# 25_LMS3_RX1_BB_ADC.net
KiCad netlist of a schematic drawn in Altium Designer
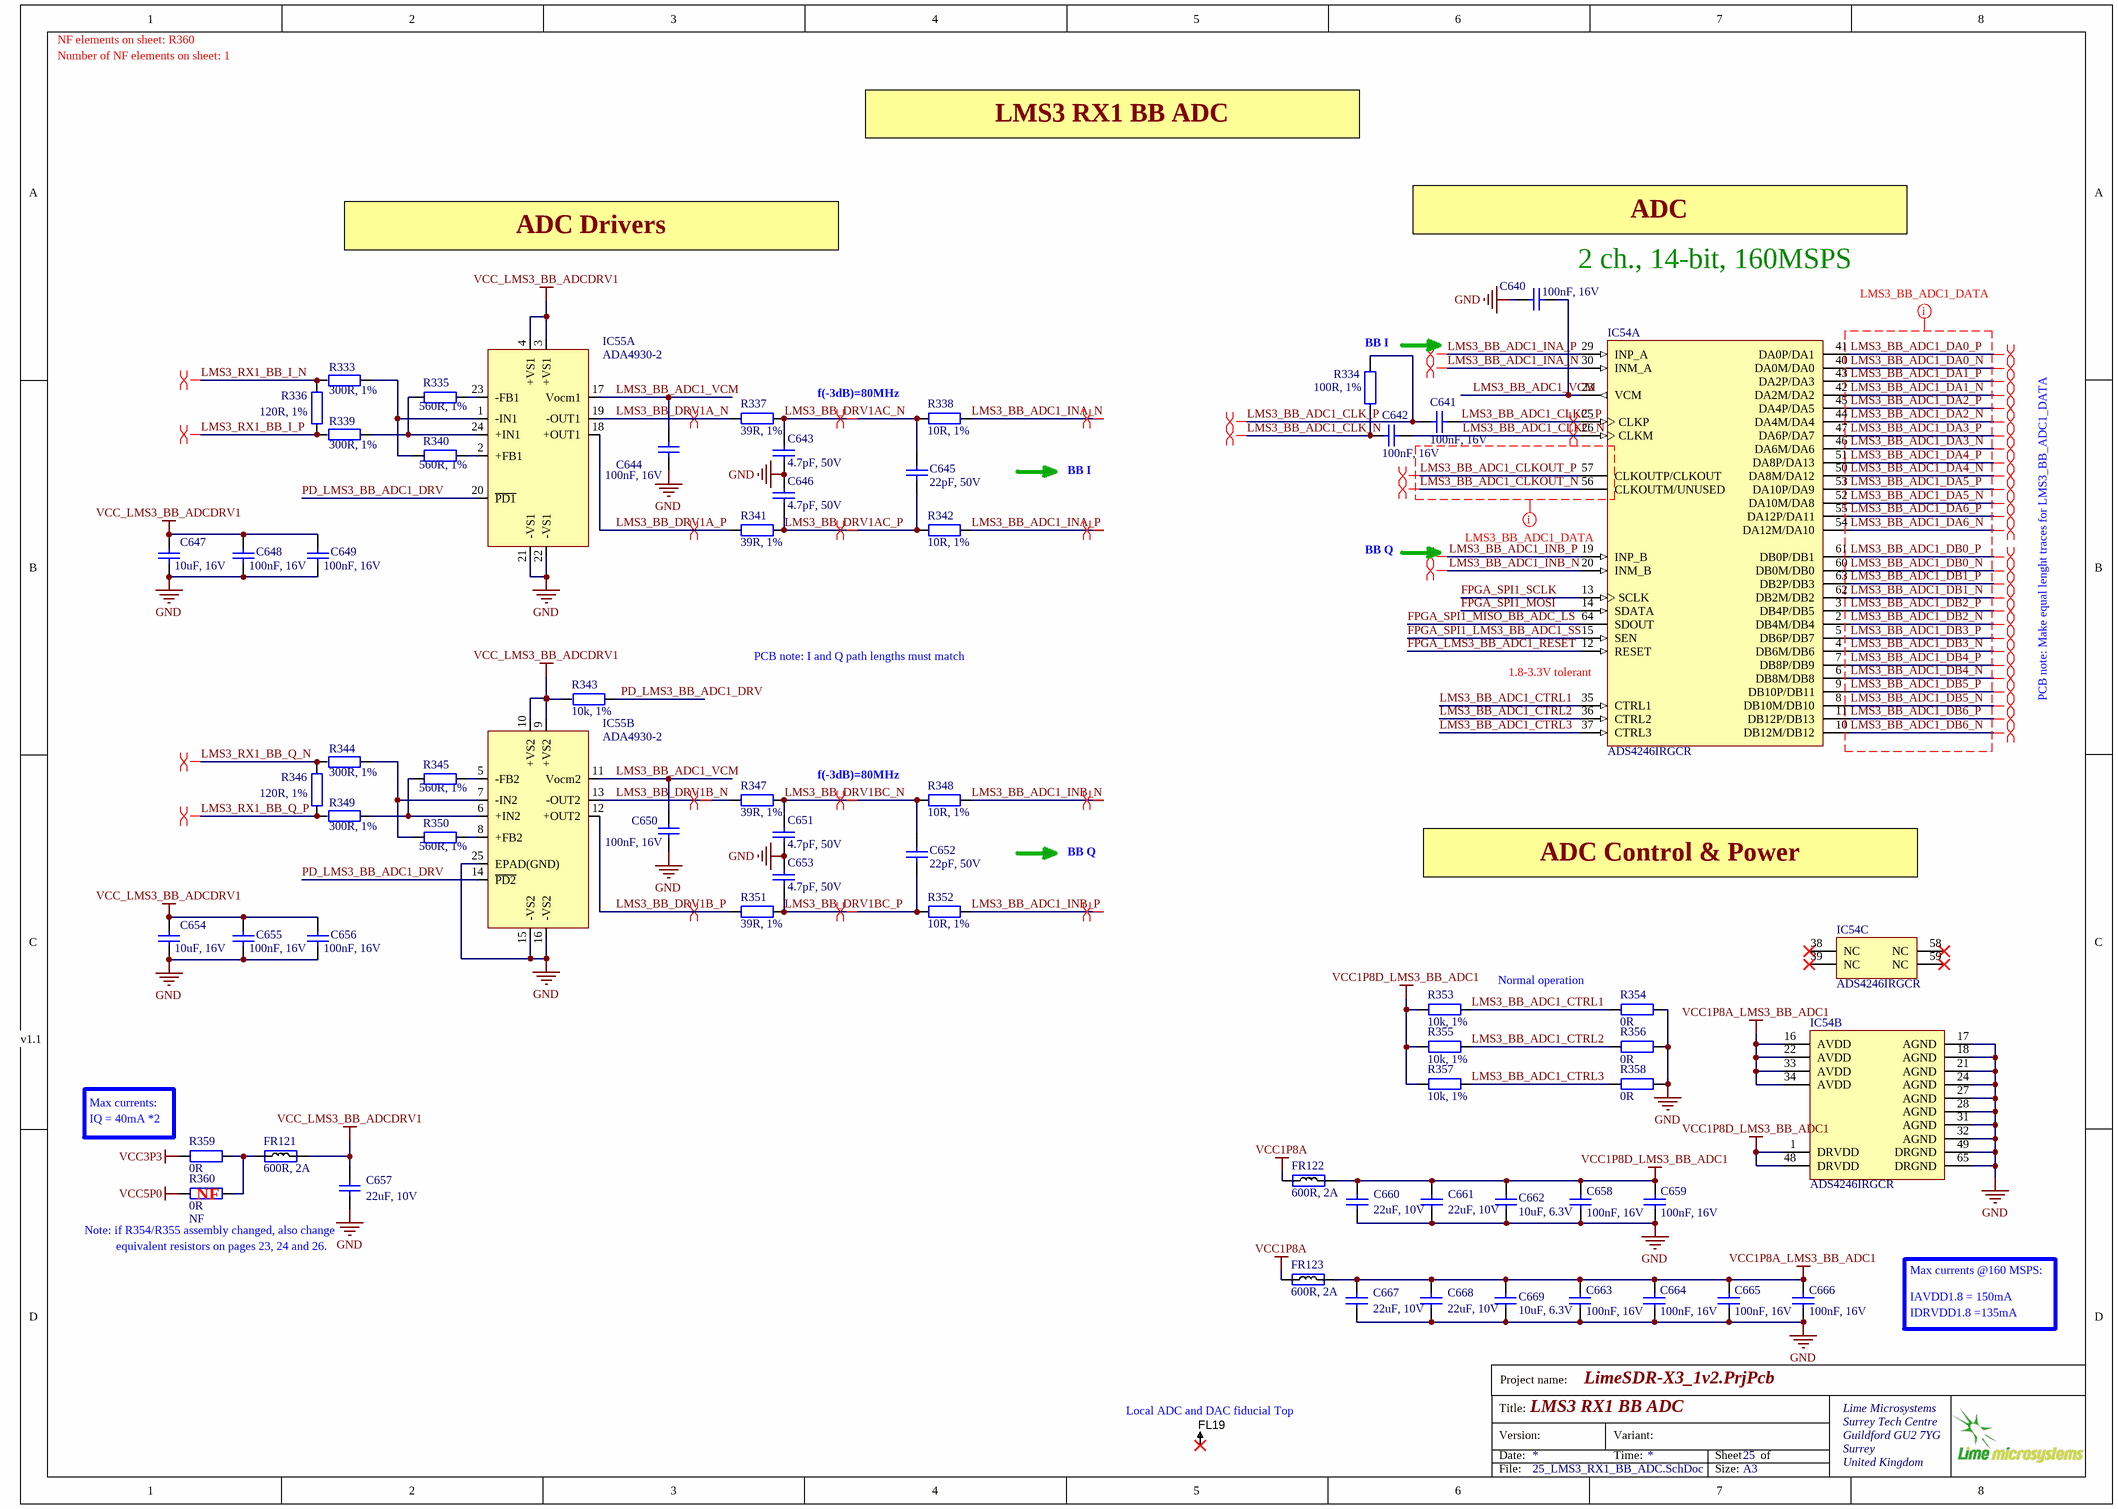
[diagram p0: 25_LMS3_RX1_BB_ADC.SchDoc]

(export (version "E")
  (design (tool "Eeschema 10.0.6"))
  (components
    (comp (ref "C640")
      (value "100nF, 16V")
      (footprint "CAP0402")
      (fields (field (name "TOLERANCE") "10 %") (field (name "MANUFACTURER") "Murata Electronics"))
      (libsource (lib "") (part "Cap_0603_2"))
    )
    (comp (ref "C641")
      (value "100nF, 16V")
      (footprint "CAP0402")
      (fields (field (name "TOLERANCE") "10 %") (field (name "MANUFACTURER") "Murata Electronics"))
      (libsource (lib "") (part "Cap_0603_2"))
    )
    (comp (ref "C642")
      (value "100nF, 16V")
      (footprint "CAP0402")
      (fields (field (name "TOLERANCE") "10 %") (field (name "MANUFACTURER") "Murata Electronics"))
      (libsource (lib "") (part "Cap_0603_1"))
    )
    (comp (ref "C643")
      (value "4.7pF, 50V")
      (footprint "CAP0402")
      (fields (field (name "MANUFACTURER") "MURATA"))
      (libsource (lib "LimeMicroAltiumLib_schLib") (part "Cap_0402"))
    )
    (comp (ref "C644")
      (value "100nF, 16V")
      (footprint "CAP0402")
      (fields (field (name "TOLERANCE") "10 %") (field (name "MANUFACTURER") "Murata Electronics"))
      (libsource (lib "") (part "Cap_0603_1"))
    )
    (comp (ref "C645")
      (value "22pF, 50V")
      (footprint "CAP0402")
      (fields (field (name "TOLERANCE") "±5%") (field (name "MANUFACTURER") "Yageo"))
      (libsource (lib "") (part "Cap_0402_1"))
    )
    (comp (ref "C646")
      (value "4.7pF, 50V")
      (footprint "CAP0402")
      (fields (field (name "MANUFACTURER") "MURATA"))
      (libsource (lib "LimeMicroAltiumLib_schLib") (part "Cap_0402"))
    )
    (comp (ref "C647")
      (value "10uF, 16V")
      (footprint "CAP0603")
      (fields (field (name "MANUFACTURER") "Yageo") (field (name "TOLERANCE") "±20%"))
      (libsource (lib "LimeMicroAltiumLib_schLib") (part "Cap_0603"))
    )
    (comp (ref "C648")
      (value "100nF, 16V")
      (footprint "CAP0402")
      (fields (field (name "TOLERANCE") "10 %") (field (name "MANUFACTURER") "Murata Electronics"))
      (libsource (lib "") (part "Cap_0603_1"))
    )
    (comp (ref "C649")
      (value "100nF, 16V")
      (footprint "CAP0402")
      (fields (field (name "TOLERANCE") "10 %") (field (name "MANUFACTURER") "Murata Electronics"))
      (libsource (lib "") (part "Cap_0603_1"))
    )
    (comp (ref "C650")
      (value "100nF, 16V")
      (footprint "CAP0402")
      (fields (field (name "TOLERANCE") "10 %") (field (name "MANUFACTURER") "Murata Electronics"))
      (libsource (lib "") (part "Cap_0603_5"))
    )
    (comp (ref "C651")
      (value "4.7pF, 50V")
      (footprint "CAP0402")
      (fields (field (name "MANUFACTURER") "MURATA"))
      (libsource (lib "LimeMicroAltiumLib_schLib") (part "Cap_0402"))
    )
    (comp (ref "C652")
      (value "22pF, 50V")
      (footprint "CAP0402")
      (fields (field (name "TOLERANCE") "±5%") (field (name "MANUFACTURER") "Yageo"))
      (libsource (lib "") (part "Cap_0402_1"))
    )
    (comp (ref "C653")
      (value "4.7pF, 50V")
      (footprint "CAP0402")
      (fields (field (name "MANUFACTURER") "MURATA"))
      (libsource (lib "LimeMicroAltiumLib_schLib") (part "Cap_0402"))
    )
    (comp (ref "C654")
      (value "10uF, 16V")
      (footprint "CAP0603")
      (fields (field (name "MANUFACTURER") "Yageo") (field (name "TOLERANCE") "±20%"))
      (libsource (lib "LimeMicroAltiumLib_schLib") (part "Cap_0603"))
    )
    (comp (ref "C655")
      (value "100nF, 16V")
      (footprint "CAP0402")
      (fields (field (name "TOLERANCE") "10 %") (field (name "MANUFACTURER") "Murata Electronics"))
      (libsource (lib "") (part "Cap_0603_1"))
    )
    (comp (ref "C656")
      (value "100nF, 16V")
      (footprint "CAP0402")
      (fields (field (name "TOLERANCE") "10 %") (field (name "MANUFACTURER") "Murata Electronics"))
      (libsource (lib "") (part "Cap_0603_1"))
    )
    (comp (ref "C657")
      (value "22uF, 10V")
      (footprint "CAP0603")
      (fields (field (name "TOLERANCE") "20 %") (field (name "MANUFACTURER") "TDK Corporation"))
      (libsource (lib "") (part "Cap_0603_3"))
    )
    (comp (ref "C658")
      (value "100nF, 16V")
      (footprint "CAP0402")
      (fields (field (name "TOLERANCE") "10 %") (field (name "MANUFACTURER") "Murata Electronics"))
      (libsource (lib "LimeFPGAboard_schLib") (part "Cap_0603"))
    )
    (comp (ref "C659")
      (value "100nF, 16V")
      (footprint "CAP0402")
      (fields (field (name "TOLERANCE") "10 %") (field (name "MANUFACTURER") "Murata Electronics"))
      (libsource (lib "LimeFPGAboard_schLib") (part "Cap_0603"))
    )
    (comp (ref "C660")
      (value "22uF, 10V")
      (footprint "CAP0603")
      (fields (field (name "TOLERANCE") "20 %") (field (name "MANUFACTURER") "TDK Corporation"))
      (libsource (lib "LimeFPGAboard_schLib") (part "Cap_0603"))
    )
    (comp (ref "C661")
      (value "22uF, 10V")
      (footprint "CAP0603")
      (fields (field (name "TOLERANCE") "20 %") (field (name "MANUFACTURER") "TDK Corporation"))
      (libsource (lib "LimeFPGAboard_schLib") (part "Cap_0603"))
    )
    (comp (ref "C662")
      (value "10uF, 6.3V")
      (footprint "CAP0603")
      (fields (field (name "TOLERANCE") "±20%") (field (name "MANUFACTURER") "Yageo"))
      (libsource (lib "") (part "Cap_0603_6"))
    )
    (comp (ref "C663")
      (value "100nF, 16V")
      (footprint "CAP0402")
      (fields (field (name "TOLERANCE") "10 %") (field (name "MANUFACTURER") "Murata Electronics"))
      (libsource (lib "") (part "Cap_0603_4"))
    )
    (comp (ref "C664")
      (value "100nF, 16V")
      (footprint "CAP0402")
      (fields (field (name "TOLERANCE") "10 %") (field (name "MANUFACTURER") "Murata Electronics"))
      (libsource (lib "") (part "Cap_0603_4"))
    )
    (comp (ref "C665")
      (value "100nF, 16V")
      (footprint "CAP0402")
      (fields (field (name "TOLERANCE") "10 %") (field (name "MANUFACTURER") "Murata Electronics"))
      (libsource (lib "") (part "Cap_0603_4"))
    )
    (comp (ref "C666")
      (value "100nF, 16V")
      (footprint "CAP0402")
      (fields (field (name "TOLERANCE") "10 %") (field (name "MANUFACTURER") "Murata Electronics"))
      (libsource (lib "") (part "Cap_0603_4"))
    )
    (comp (ref "C667")
      (value "22uF, 10V")
      (footprint "CAP0603")
      (fields (field (name "TOLERANCE") "20 %") (field (name "MANUFACTURER") "TDK Corporation"))
      (libsource (lib "") (part "Cap_0603_4"))
    )
    (comp (ref "C668")
      (value "22uF, 10V")
      (footprint "CAP0603")
      (fields (field (name "TOLERANCE") "20 %") (field (name "MANUFACTURER") "TDK Corporation"))
      (libsource (lib "") (part "Cap_0603_4"))
    )
    (comp (ref "C669")
      (value "10uF, 6.3V")
      (footprint "CAP0603")
      (fields (field (name "TOLERANCE") "±20%") (field (name "MANUFACTURER") "Yageo"))
      (libsource (lib "") (part "Cap_0603_7"))
    )
    (comp (ref "FL19")
      (value "Fiducial")
      (footprint "Fiducial_local")
      (libsource (lib "LimeMicroAltiumLib_schLib") (part "Fiducial"))
    )
    (comp (ref "FR121")
      (value "600R, 2A")
      (footprint "RES0805")
      (fields (field (name "MANUFACTURER") "TDK Corporation"))
      (libsource (lib "LimeMicroAltiumLib_schLib") (part "Ferrite"))
    )
    (comp (ref "FR122")
      (value "600R, 2A")
      (footprint "RES0805")
      (fields (field (name "MANUFACTURER") "TDK Corporation"))
      (libsource (lib "LimeFPGAboard_schLib") (part "Ferrite"))
    )
    (comp (ref "FR123")
      (value "600R, 2A")
      (footprint "RES0805")
      (fields (field (name "MANUFACTURER") "TDK Corporation"))
      (libsource (lib "LimeFPGAboard_schLib") (part "Ferrite"))
    )
    (comp (ref "IC54")
      (value "ADS4246IRGCR")
      (footprint "TI-RGC64-7400X7400TP_V")
      (description "14-Bit 160 MSPS Dual Low Power ADC, -40 to 85 degC, 64-pin QFN (RGC64), Green (RoHS & no Sb/Br)")
      (fields (field (name "MANUFACTURER") "Texas Instruments"))
      (libsource (lib "") (part "ADS4246IRGCR_1"))
    )
    (comp (ref "IC55")
      (value "ADA4930-2")
      (footprint "ADA4930-2_LFCSP-24")
      (fields (field (name "MANUFACTURER") "Analog Devices Inc."))
      (libsource (lib "LimeMicroAltiumLib_schLib") (part "ADA4930-2"))
    )
    (comp (ref "R333")
      (value "300R, 1%")
      (footprint "RES0402")
      (fields (field (name "TOLERANCE") "±1%") (field (name "MANUFACTURER") "Vishay Dale"))
      (libsource (lib "LimeFPGAboard_schLib") (part "Res_0402"))
    )
    (comp (ref "R334")
      (value "100R, 1%")
      (footprint "RES0402")
      (fields (field (name "TOLERANCE") "±1%") (field (name "MANUFACTURER") "Stackpole Electronics Inc."))
      (libsource (lib "LimeFPGAboard_schLib") (part "Res_0402"))
    )
    (comp (ref "R335")
      (value "560R, 1%")
      (footprint "RES0402")
      (fields (field (name "TOLERANCE") "±1%") (field (name "MANUFACTURER") "Vishay Dale"))
      (libsource (lib "LimeFPGAboard_schLib") (part "Res_0402"))
    )
    (comp (ref "R336")
      (value "120R, 1%")
      (footprint "RES0402")
      (fields (field (name "MANUFACTURER") "Yageo") (field (name "TOLERANCE") "1%"))
      (libsource (lib "") (part "Res_0402_1"))
    )
    (comp (ref "R337")
      (value "39R, 1%")
      (footprint "RES0402")
      (fields (field (name "MANUFACTURER") "Yageo") (field (name "TOLERANCE") "1%"))
      (libsource (lib "LimeMicroAltiumLib_schLib") (part "Res_0402"))
    )
    (comp (ref "R338")
      (value "10R, 1%")
      (footprint "RES0402")
      (fields (field (name "TOLERANCE") "1%"))
      (libsource (lib "LimeMicroAltiumLib_schLib") (part "Res_0402"))
    )
    (comp (ref "R339")
      (value "300R, 1%")
      (footprint "RES0402")
      (fields (field (name "TOLERANCE") "±1%") (field (name "MANUFACTURER") "Vishay Dale"))
      (libsource (lib "LimeFPGAboard_schLib") (part "Res_0402"))
    )
    (comp (ref "R340")
      (value "560R, 1%")
      (footprint "RES0402")
      (fields (field (name "TOLERANCE") "±1%") (field (name "MANUFACTURER") "Vishay Dale"))
      (libsource (lib "LimeFPGAboard_schLib") (part "Res_0402"))
    )
    (comp (ref "R341")
      (value "39R, 1%")
      (footprint "RES0402")
      (fields (field (name "MANUFACTURER") "Yageo") (field (name "TOLERANCE") "1%"))
      (libsource (lib "LimeMicroAltiumLib_schLib") (part "Res_0402"))
    )
    (comp (ref "R342")
      (value "10R, 1%")
      (footprint "RES0402")
      (fields (field (name "TOLERANCE") "1%"))
      (libsource (lib "LimeMicroAltiumLib_schLib") (part "Res_0402"))
    )
    (comp (ref "R343")
      (value "10k, 1%")
      (footprint "RES0402")
      (fields (field (name "MANUFACTURER") "Yageo") (field (name "TOLERANCE") "±1%"))
      (libsource (lib "LimeMicroAltiumLib_schLib") (part "Res_0402"))
    )
    (comp (ref "R344")
      (value "300R, 1%")
      (footprint "RES0402")
      (fields (field (name "TOLERANCE") "±1%") (field (name "MANUFACTURER") "Vishay Dale"))
      (libsource (lib "LimeFPGAboard_schLib") (part "Res_0402"))
    )
    (comp (ref "R345")
      (value "560R, 1%")
      (footprint "RES0402")
      (fields (field (name "TOLERANCE") "±1%") (field (name "MANUFACTURER") "Vishay Dale"))
      (libsource (lib "LimeFPGAboard_schLib") (part "Res_0402"))
    )
    (comp (ref "R346")
      (value "120R, 1%")
      (footprint "RES0402")
      (fields (field (name "MANUFACTURER") "Yageo") (field (name "TOLERANCE") "1%"))
      (libsource (lib "") (part "Res_0402_1"))
    )
    (comp (ref "R347")
      (value "39R, 1%")
      (footprint "RES0402")
      (fields (field (name "MANUFACTURER") "Yageo") (field (name "TOLERANCE") "1%"))
      (libsource (lib "LimeMicroAltiumLib_schLib") (part "Res_0402"))
    )
    (comp (ref "R348")
      (value "10R, 1%")
      (footprint "RES0402")
      (fields (field (name "TOLERANCE") "1%"))
      (libsource (lib "LimeMicroAltiumLib_schLib") (part "Res_0402"))
    )
    (comp (ref "R349")
      (value "300R, 1%")
      (footprint "RES0402")
      (fields (field (name "TOLERANCE") "±1%") (field (name "MANUFACTURER") "Vishay Dale"))
      (libsource (lib "LimeFPGAboard_schLib") (part "Res_0402"))
    )
    (comp (ref "R350")
      (value "560R, 1%")
      (footprint "RES0402")
      (fields (field (name "TOLERANCE") "±1%") (field (name "MANUFACTURER") "Vishay Dale"))
      (libsource (lib "LimeFPGAboard_schLib") (part "Res_0402"))
    )
    (comp (ref "R351")
      (value "39R, 1%")
      (footprint "RES0402")
      (fields (field (name "MANUFACTURER") "Yageo") (field (name "TOLERANCE") "1%"))
      (libsource (lib "LimeMicroAltiumLib_schLib") (part "Res_0402"))
    )
    (comp (ref "R352")
      (value "10R, 1%")
      (footprint "RES0402")
      (fields (field (name "TOLERANCE") "1%"))
      (libsource (lib "LimeMicroAltiumLib_schLib") (part "Res_0402"))
    )
    (comp (ref "R353")
      (value "10k, 1%")
      (footprint "RES0402")
      (fields (field (name "MANUFACTURER") "Yageo") (field (name "TOLERANCE") "±1%"))
      (libsource (lib "LimeMicroAltiumLib_schLib") (part "Res_0402"))
    )
    (comp (ref "R354")
      (value "0R")
      (footprint "RES0402")
      (fields (field (name "MANUFACTURER") "Yageo"))
      (libsource (lib "LimeFPGAboard_schLib") (part "Res_0402"))
    )
    (comp (ref "R355")
      (value "10k, 1%")
      (footprint "RES0402")
      (fields (field (name "MANUFACTURER") "Yageo") (field (name "TOLERANCE") "±1%"))
      (libsource (lib "LimeMicroAltiumLib_schLib") (part "Res_0402"))
    )
    (comp (ref "R356")
      (value "0R")
      (footprint "RES0402")
      (fields (field (name "MANUFACTURER") "Yageo"))
      (libsource (lib "LimeFPGAboard_schLib") (part "Res_0402"))
    )
    (comp (ref "R357")
      (value "10k, 1%")
      (footprint "RES0402")
      (fields (field (name "MANUFACTURER") "Yageo") (field (name "TOLERANCE") "±1%"))
      (libsource (lib "LimeMicroAltiumLib_schLib") (part "Res_0402"))
    )
    (comp (ref "R358")
      (value "0R")
      (footprint "RES0402")
      (fields (field (name "MANUFACTURER") "Yageo"))
      (libsource (lib "LimeFPGAboard_schLib") (part "Res_0402"))
    )
    (comp (ref "R359")
      (value "0R")
      (footprint "RES0402")
      (fields (field (name "MANUFACTURER") "Yageo") (field (name "TOLERANCE") "Jumper"))
      (libsource (lib "LimeMicroAltiumLib_schLib") (part "Res_0402"))
    )
    (comp (ref "R360")
      (value "0R")
      (footprint "RES0402")
      (fields
        (field (name "ASSEMBLY INFO") "NF")
        (field (name "MANUFACTURER") "Yageo")
        (field (name "TOLERANCE") "Jumper")
      )
      (libsource (lib "LimeMicroAltiumLib_schLib") (part "Res_0402"))
    )
  )
  (nets
    (net (code "1") (name "/FPGA_LMS3_BB_ADC1_RESET") (class "Default")
      (node (ref "IC54") (pin "12") (pinfunction "RESET_12") (pintype "input"))
    )
    (net (code "2") (name "/FPGA_SPI1_LMS3_BB_ADC1_SS") (class "Default")
      (node (ref "IC54") (pin "15") (pinfunction "SEN_15") (pintype "input"))
    )
    (net (code "3") (name "/FPGA_SPI1_MISO_BB_ADC_LS") (class "Default")
      (node (ref "IC54") (pin "64") (pinfunction "SDOUT_64") (pintype "tri_state"))
    )
    (net (code "4") (name "/FPGA_SPI1_MOSI") (class "Default")
      (node (ref "IC54") (pin "14") (pinfunction "SDATA_14") (pintype "input"))
    )
    (net (code "5") (name "/FPGA_SPI1_SCLK") (class "Default")
      (node (ref "IC54") (pin "13") (pinfunction "SCLK_13") (pintype "input"))
    )
    (net (code "6") (name "/LMS3_BB_ADC1_CLKC_N") (class "Default")
      (node (ref "C642") (pin "1") (pinfunction "1_1") (pintype "passive"))
      (node (ref "IC54") (pin "26") (pinfunction "CLKM_26") (pintype "input"))
    )
    (net (code "7") (name "/LMS3_BB_ADC1_CLKC_P") (class "Default")
      (node (ref "C641") (pin "1") (pinfunction "1_1") (pintype "passive"))
      (node (ref "IC54") (pin "25") (pinfunction "CLKP_25") (pintype "input"))
    )
    (net (code "8") (name "/LMS3_BB_ADC1_CLKOUT_N") (class "Default")
      (node (ref "IC54") (pin "56") (pinfunction "CLKOUTM/UNUSED_56") (pintype "tri_state"))
    )
    (net (code "9") (name "/LMS3_BB_ADC1_CLKOUT_P") (class "Default")
      (node (ref "IC54") (pin "57") (pinfunction "CLKOUTP/CLKOUT_57") (pintype "tri_state"))
    )
    (net (code "10") (name "/LMS3_BB_ADC1_CLK_N") (class "Default")
      (node (ref "C642") (pin "2") (pinfunction "2_2") (pintype "passive"))
      (node (ref "R334") (pin "1") (pinfunction "1_1") (pintype "passive"))
    )
    (net (code "11") (name "/LMS3_BB_ADC1_CLK_P") (class "Default")
      (node (ref "C641") (pin "2") (pinfunction "2_2") (pintype "passive"))
      (node (ref "R334") (pin "2") (pinfunction "2_2") (pintype "passive"))
    )
    (net (code "12") (name "/LMS3_BB_ADC1_CTRL1") (class "Default")
      (node (ref "IC54") (pin "35") (pinfunction "CTRL1_35") (pintype "input"))
      (node (ref "R353") (pin "1") (pinfunction "1_1") (pintype "passive"))
      (node (ref "R354") (pin "2") (pinfunction "2_2") (pintype "passive"))
    )
    (net (code "13") (name "/LMS3_BB_ADC1_CTRL2") (class "Default")
      (node (ref "IC54") (pin "36") (pinfunction "CTRL2_36") (pintype "input"))
      (node (ref "R355") (pin "1") (pinfunction "1_1") (pintype "passive"))
      (node (ref "R356") (pin "2") (pinfunction "2_2") (pintype "passive"))
    )
    (net (code "14") (name "/LMS3_BB_ADC1_CTRL3") (class "Default")
      (node (ref "IC54") (pin "37") (pinfunction "CTRL3_37") (pintype "input"))
      (node (ref "R357") (pin "1") (pinfunction "1_1") (pintype "passive"))
      (node (ref "R358") (pin "2") (pinfunction "2_2") (pintype "passive"))
    )
    (net (code "15") (name "/LMS3_BB_ADC1_DA0_N") (class "Default")
      (node (ref "IC54") (pin "40") (pinfunction "DA0M/DA0_40") (pintype "tri_state"))
    )
    (net (code "16") (name "/LMS3_BB_ADC1_DA0_P") (class "Default")
      (node (ref "IC54") (pin "41") (pinfunction "DA0P/DA1_41") (pintype "tri_state"))
    )
    (net (code "17") (name "/LMS3_BB_ADC1_DA1_N") (class "Default")
      (node (ref "IC54") (pin "42") (pinfunction "DA2M/DA2_42") (pintype "tri_state"))
    )
    (net (code "18") (name "/LMS3_BB_ADC1_DA1_P") (class "Default")
      (node (ref "IC54") (pin "43") (pinfunction "DA2P/DA3_43") (pintype "tri_state"))
    )
    (net (code "19") (name "/LMS3_BB_ADC1_DA2_N") (class "Default")
      (node (ref "IC54") (pin "44") (pinfunction "DA4M/DA4_44") (pintype "tri_state"))
    )
    (net (code "20") (name "/LMS3_BB_ADC1_DA2_P") (class "Default")
      (node (ref "IC54") (pin "45") (pinfunction "DA4P/DA5_45") (pintype "tri_state"))
    )
    (net (code "21") (name "/LMS3_BB_ADC1_DA3_N") (class "Default")
      (node (ref "IC54") (pin "46") (pinfunction "DA6M/DA6_46") (pintype "tri_state"))
    )
    (net (code "22") (name "/LMS3_BB_ADC1_DA3_P") (class "Default")
      (node (ref "IC54") (pin "47") (pinfunction "DA6P/DA7_47") (pintype "tri_state"))
    )
    (net (code "23") (name "/LMS3_BB_ADC1_DA4_N") (class "Default")
      (node (ref "IC54") (pin "50") (pinfunction "DA8M/DA12_50") (pintype "tri_state"))
    )
    (net (code "24") (name "/LMS3_BB_ADC1_DA4_P") (class "Default")
      (node (ref "IC54") (pin "51") (pinfunction "DA8P/DA13_51") (pintype "tri_state"))
    )
    (net (code "25") (name "/LMS3_BB_ADC1_DA5_N") (class "Default")
      (node (ref "IC54") (pin "52") (pinfunction "DA10M/DA8_52") (pintype "tri_state"))
    )
    (net (code "26") (name "/LMS3_BB_ADC1_DA5_P") (class "Default")
      (node (ref "IC54") (pin "53") (pinfunction "DA10P/DA9_53") (pintype "tri_state"))
    )
    (net (code "27") (name "/LMS3_BB_ADC1_DA6_N") (class "Default")
      (node (ref "IC54") (pin "54") (pinfunction "DA12M/DA10_54") (pintype "tri_state"))
    )
    (net (code "28") (name "/LMS3_BB_ADC1_DA6_P") (class "Default")
      (node (ref "IC54") (pin "55") (pinfunction "DA12P/DA11_55") (pintype "tri_state"))
    )
    (net (code "29") (name "/LMS3_BB_ADC1_DB0_N") (class "Default")
      (node (ref "IC54") (pin "60") (pinfunction "DB0M/DB0_60") (pintype "tri_state"))
    )
    (net (code "30") (name "/LMS3_BB_ADC1_DB0_P") (class "Default")
      (node (ref "IC54") (pin "61") (pinfunction "DB0P/DB1_61") (pintype "tri_state"))
    )
    (net (code "31") (name "/LMS3_BB_ADC1_DB1_N") (class "Default")
      (node (ref "IC54") (pin "62") (pinfunction "DB2M/DB2_62") (pintype "tri_state"))
    )
    (net (code "32") (name "/LMS3_BB_ADC1_DB1_P") (class "Default")
      (node (ref "IC54") (pin "63") (pinfunction "DB2P/DB3_63") (pintype "tri_state"))
    )
    (net (code "33") (name "/LMS3_BB_ADC1_DB2_N") (class "Default")
      (node (ref "IC54") (pin "2") (pinfunction "DB4M/DB4_2") (pintype "tri_state"))
    )
    (net (code "34") (name "/LMS3_BB_ADC1_DB2_P") (class "Default")
      (node (ref "IC54") (pin "3") (pinfunction "DB4P/DB5_3") (pintype "tri_state"))
    )
    (net (code "35") (name "/LMS3_BB_ADC1_DB3_N") (class "Default")
      (node (ref "IC54") (pin "4") (pinfunction "DB6M/DB6_4") (pintype "tri_state"))
    )
    (net (code "36") (name "/LMS3_BB_ADC1_DB3_P") (class "Default")
      (node (ref "IC54") (pin "5") (pinfunction "DB6P/DB7_5") (pintype "tri_state"))
    )
    (net (code "37") (name "/LMS3_BB_ADC1_DB4_N") (class "Default")
      (node (ref "IC54") (pin "6") (pinfunction "DB8M/DB8_6") (pintype "tri_state"))
    )
    (net (code "38") (name "/LMS3_BB_ADC1_DB4_P") (class "Default")
      (node (ref "IC54") (pin "7") (pinfunction "DB8P/DB9_7") (pintype "tri_state"))
    )
    (net (code "39") (name "/LMS3_BB_ADC1_DB5_N") (class "Default")
      (node (ref "IC54") (pin "8") (pinfunction "DB10M/DB10_8") (pintype "tri_state"))
    )
    (net (code "40") (name "/LMS3_BB_ADC1_DB5_P") (class "Default")
      (node (ref "IC54") (pin "9") (pinfunction "DB10P/DB11_9") (pintype "tri_state"))
    )
    (net (code "41") (name "/LMS3_BB_ADC1_DB6_N") (class "Default")
      (node (ref "IC54") (pin "10") (pinfunction "DB12M/DB12_10") (pintype "tri_state"))
    )
    (net (code "42") (name "/LMS3_BB_ADC1_DB6_P") (class "Default")
      (node (ref "IC54") (pin "11") (pinfunction "DB12P/DB13_11") (pintype "tri_state"))
    )
    (net (code "43") (name "/LMS3_BB_ADC1_INA_N") (class "Default")
      (node (ref "IC54") (pin "30") (pinfunction "INM_A_30") (pintype "input"))
      (node (ref "R338") (pin "1") (pinfunction "1_1") (pintype "passive"))
    )
    (net (code "44") (name "/LMS3_BB_ADC1_INA_P") (class "Default")
      (node (ref "IC54") (pin "29") (pinfunction "INP_A_29") (pintype "input"))
      (node (ref "R342") (pin "1") (pinfunction "1_1") (pintype "passive"))
    )
    (net (code "45") (name "/LMS3_BB_ADC1_INB_N") (class "Default")
      (node (ref "IC54") (pin "20") (pinfunction "INM_B_20") (pintype "input"))
      (node (ref "R348") (pin "1") (pinfunction "1_1") (pintype "passive"))
    )
    (net (code "46") (name "/LMS3_BB_ADC1_INB_P") (class "Default")
      (node (ref "IC54") (pin "19") (pinfunction "INP_B_19") (pintype "input"))
      (node (ref "R352") (pin "1") (pinfunction "1_1") (pintype "passive"))
    )
    (net (code "47") (name "/LMS3_BB_ADC1_VCM") (class "Default")
      (node (ref "C640") (pin "2") (pinfunction "2_2") (pintype "passive"))
      (node (ref "C644") (pin "1") (pinfunction "1_1") (pintype "passive"))
      (node (ref "C650") (pin "1") (pinfunction "1_1") (pintype "passive"))
      (node (ref "IC54") (pin "23") (pinfunction "VCM_23") (pintype "output"))
      (node (ref "IC55") (pin "11") (pinfunction "Vocm2_11") (pintype "input"))
      (node (ref "IC55") (pin "17") (pinfunction "Vocm1_17") (pintype "input"))
    )
    (net (code "48") (name "/LMS3_BB_DRV1AC_N") (class "Default")
      (node (ref "C643") (pin "1") (pinfunction "1_1") (pintype "passive"))
      (node (ref "C645") (pin "1") (pinfunction "1_1") (pintype "passive"))
      (node (ref "R337") (pin "1") (pinfunction "1_1") (pintype "passive"))
      (node (ref "R338") (pin "2") (pinfunction "2_2") (pintype "passive"))
    )
    (net (code "49") (name "/LMS3_BB_DRV1AC_P") (class "Default")
      (node (ref "C645") (pin "2") (pinfunction "2_2") (pintype "passive"))
      (node (ref "C646") (pin "2") (pinfunction "2_2") (pintype "passive"))
      (node (ref "R341") (pin "1") (pinfunction "1_1") (pintype "passive"))
      (node (ref "R342") (pin "2") (pinfunction "2_2") (pintype "passive"))
    )
    (net (code "50") (name "/LMS3_BB_DRV1A_N") (class "Default")
      (node (ref "IC55") (pin "19") (pinfunction "-OUT1_19") (pintype "output"))
      (node (ref "R337") (pin "2") (pinfunction "2_2") (pintype "passive"))
    )
    (net (code "51") (name "/LMS3_BB_DRV1A_P") (class "Default")
      (node (ref "IC55") (pin "18") (pinfunction "+OUT1_18") (pintype "output"))
      (node (ref "R341") (pin "2") (pinfunction "2_2") (pintype "passive"))
    )
    (net (code "52") (name "/LMS3_BB_DRV1BC_N") (class "Default")
      (node (ref "C651") (pin "1") (pinfunction "1_1") (pintype "passive"))
      (node (ref "C652") (pin "1") (pinfunction "1_1") (pintype "passive"))
      (node (ref "R347") (pin "1") (pinfunction "1_1") (pintype "passive"))
      (node (ref "R348") (pin "2") (pinfunction "2_2") (pintype "passive"))
    )
    (net (code "53") (name "/LMS3_BB_DRV1BC_P") (class "Default")
      (node (ref "C652") (pin "2") (pinfunction "2_2") (pintype "passive"))
      (node (ref "C653") (pin "2") (pinfunction "2_2") (pintype "passive"))
      (node (ref "R351") (pin "1") (pinfunction "1_1") (pintype "passive"))
      (node (ref "R352") (pin "2") (pinfunction "2_2") (pintype "passive"))
    )
    (net (code "54") (name "/LMS3_BB_DRV1B_N") (class "Default")
      (node (ref "IC55") (pin "13") (pinfunction "-OUT2_13") (pintype "output"))
      (node (ref "R347") (pin "2") (pinfunction "2_2") (pintype "passive"))
    )
    (net (code "55") (name "/LMS3_BB_DRV1B_P") (class "Default")
      (node (ref "IC55") (pin "12") (pinfunction "+OUT2_12") (pintype "output"))
      (node (ref "R351") (pin "2") (pinfunction "2_2") (pintype "passive"))
    )
    (net (code "56") (name "/LMS3_RX1_BB_I_N") (class "Default")
      (node (ref "R333") (pin "2") (pinfunction "2_2") (pintype "passive"))
      (node (ref "R336") (pin "2") (pinfunction "2_2") (pintype "passive"))
    )
    (net (code "57") (name "/LMS3_RX1_BB_I_P") (class "Default")
      (node (ref "R336") (pin "1") (pinfunction "1_1") (pintype "passive"))
      (node (ref "R339") (pin "2") (pinfunction "2_2") (pintype "passive"))
    )
    (net (code "58") (name "/LMS3_RX1_BB_Q_N") (class "Default")
      (node (ref "R344") (pin "2") (pinfunction "2_2") (pintype "passive"))
      (node (ref "R346") (pin "2") (pinfunction "2_2") (pintype "passive"))
    )
    (net (code "59") (name "/LMS3_RX1_BB_Q_P") (class "Default")
      (node (ref "R346") (pin "1") (pinfunction "1_1") (pintype "passive"))
      (node (ref "R349") (pin "2") (pinfunction "2_2") (pintype "passive"))
    )
    (net (code "60") (name "/PD_LMS3_BB_ADC1_DRV") (class "Default")
      (node (ref "IC55") (pin "14") (pinfunction "~{PD2}_14") (pintype "input"))
      (node (ref "IC55") (pin "20") (pinfunction "~{PD1}_20") (pintype "input"))
      (node (ref "R343") (pin "1") (pinfunction "1_1") (pintype "passive"))
    )
    (net (code "61") (name "GND") (class "Default")
      (node (ref "C640") (pin "1") (pinfunction "1_1") (pintype "passive"))
      (node (ref "C643") (pin "2") (pinfunction "2_2") (pintype "passive"))
      (node (ref "C644") (pin "2") (pinfunction "2_2") (pintype "passive"))
      (node (ref "C646") (pin "1") (pinfunction "1_1") (pintype "passive"))
      (node (ref "C647") (pin "1") (pinfunction "1_1") (pintype "passive"))
      (node (ref "C648") (pin "2") (pinfunction "2_2") (pintype "passive"))
      (node (ref "C649") (pin "2") (pinfunction "2_2") (pintype "passive"))
      (node (ref "C650") (pin "2") (pinfunction "2_2") (pintype "passive"))
      (node (ref "C651") (pin "2") (pinfunction "2_2") (pintype "passive"))
      (node (ref "C653") (pin "1") (pinfunction "1_1") (pintype "passive"))
      (node (ref "C654") (pin "1") (pinfunction "1_1") (pintype "passive"))
      (node (ref "C655") (pin "2") (pinfunction "2_2") (pintype "passive"))
      (node (ref "C656") (pin "2") (pinfunction "2_2") (pintype "passive"))
      (node (ref "C657") (pin "1") (pinfunction "1_1") (pintype "passive"))
      (node (ref "C658") (pin "1") (pinfunction "1_1") (pintype "passive"))
      (node (ref "C659") (pin "1") (pinfunction "1_1") (pintype "passive"))
      (node (ref "C660") (pin "1") (pinfunction "1_1") (pintype "passive"))
      (node (ref "C661") (pin "1") (pinfunction "1_1") (pintype "passive"))
      (node (ref "C662") (pin "2") (pinfunction "2_2") (pintype "passive"))
      (node (ref "C663") (pin "1") (pinfunction "1_1") (pintype "passive"))
      (node (ref "C664") (pin "1") (pinfunction "1_1") (pintype "passive"))
      (node (ref "C665") (pin "1") (pinfunction "1_1") (pintype "passive"))
      (node (ref "C666") (pin "1") (pinfunction "1_1") (pintype "passive"))
      (node (ref "C667") (pin "1") (pinfunction "1_1") (pintype "passive"))
      (node (ref "C668") (pin "1") (pinfunction "1_1") (pintype "passive"))
      (node (ref "C669") (pin "2") (pinfunction "2_2") (pintype "passive"))
      (node (ref "IC54") (pin "17") (pinfunction "AGND_17") (pintype "power_in"))
      (node (ref "IC54") (pin "18") (pinfunction "AGND_18") (pintype "power_in"))
      (node (ref "IC54") (pin "21") (pinfunction "AGND_21") (pintype "power_in"))
      (node (ref "IC54") (pin "24") (pinfunction "AGND_24") (pintype "power_in"))
      (node (ref "IC54") (pin "27") (pinfunction "AGND_27") (pintype "power_in"))
      (node (ref "IC54") (pin "28") (pinfunction "AGND_28") (pintype "power_in"))
      (node (ref "IC54") (pin "31") (pinfunction "AGND_31") (pintype "power_in"))
      (node (ref "IC54") (pin "32") (pinfunction "AGND_32") (pintype "power_in"))
      (node (ref "IC54") (pin "49") (pinfunction "DRGND_49") (pintype "power_in"))
      (node (ref "IC54") (pin "65") (pinfunction "DRGND_65") (pintype "power_in"))
      (node (ref "IC55") (pin "15") (pinfunction "-VS2_15") (pintype "power_in"))
      (node (ref "IC55") (pin "16") (pinfunction "-VS2_16") (pintype "power_in"))
      (node (ref "IC55") (pin "21") (pinfunction "-VS1_21") (pintype "power_in"))
      (node (ref "IC55") (pin "22") (pinfunction "-VS1_22") (pintype "power_in"))
      (node (ref "IC55") (pin "25") (pinfunction "EPAD(GND)_25") (pintype "passive"))
      (node (ref "R354") (pin "1") (pinfunction "1_1") (pintype "passive"))
      (node (ref "R356") (pin "1") (pinfunction "1_1") (pintype "passive"))
      (node (ref "R358") (pin "1") (pinfunction "1_1") (pintype "passive"))
    )
    (net (code "62") (name "Net-(FR121-Pad1)") (class "Default")
      (node (ref "FR121") (pin "1") (pinfunction "1_1") (pintype "passive"))
      (node (ref "R359") (pin "1") (pinfunction "1_1") (pintype "passive"))
      (node (ref "R360") (pin "1") (pinfunction "1_1") (pintype "passive"))
    )
    (net (code "63") (name "Net-(IC55A-+FB1)") (class "Default")
      (node (ref "IC55") (pin "2") (pinfunction "+FB1_2") (pintype "output"))
      (node (ref "R340") (pin "1") (pinfunction "1_1") (pintype "passive"))
    )
    (net (code "64") (name "Net-(IC55A-+IN1)") (class "Default")
      (node (ref "IC55") (pin "24") (pinfunction "+IN1_24") (pintype "input"))
      (node (ref "R335") (pin "2") (pinfunction "2_2") (pintype "passive"))
      (node (ref "R339") (pin "1") (pinfunction "1_1") (pintype "passive"))
    )
    (net (code "65") (name "Net-(IC55A--FB1)") (class "Default")
      (node (ref "IC55") (pin "23") (pinfunction "-FB1_23") (pintype "output"))
      (node (ref "R335") (pin "1") (pinfunction "1_1") (pintype "passive"))
    )
    (net (code "66") (name "Net-(IC55A--IN1)") (class "Default")
      (node (ref "IC55") (pin "1") (pinfunction "-IN1_1") (pintype "input"))
      (node (ref "R333") (pin "1") (pinfunction "1_1") (pintype "passive"))
      (node (ref "R340") (pin "2") (pinfunction "2_2") (pintype "passive"))
    )
    (net (code "67") (name "Net-(IC55B-+FB2)") (class "Default")
      (node (ref "IC55") (pin "8") (pinfunction "+FB2_8") (pintype "output"))
      (node (ref "R350") (pin "1") (pinfunction "1_1") (pintype "passive"))
    )
    (net (code "68") (name "Net-(IC55B-+IN2)") (class "Default")
      (node (ref "IC55") (pin "6") (pinfunction "+IN2_6") (pintype "input"))
      (node (ref "R345") (pin "2") (pinfunction "2_2") (pintype "passive"))
      (node (ref "R349") (pin "1") (pinfunction "1_1") (pintype "passive"))
    )
    (net (code "69") (name "Net-(IC55B--FB2)") (class "Default")
      (node (ref "IC55") (pin "5") (pinfunction "-FB2_5") (pintype "output"))
      (node (ref "R345") (pin "1") (pinfunction "1_1") (pintype "passive"))
    )
    (net (code "70") (name "Net-(IC55B--IN2)") (class "Default")
      (node (ref "IC55") (pin "7") (pinfunction "-IN2_7") (pintype "input"))
      (node (ref "R344") (pin "1") (pinfunction "1_1") (pintype "passive"))
      (node (ref "R350") (pin "2") (pinfunction "2_2") (pintype "passive"))
    )
    (net (code "71") (name "VCC1P8A") (class "Default")
      (node (ref "FR122") (pin "1") (pinfunction "1_1") (pintype "passive"))
      (node (ref "FR123") (pin "1") (pinfunction "1_1") (pintype "passive"))
    )
    (net (code "72") (name "VCC1P8A_LMS3_BB_ADC1") (class "Default")
      (node (ref "C663") (pin "2") (pinfunction "2_2") (pintype "passive"))
      (node (ref "C664") (pin "2") (pinfunction "2_2") (pintype "passive"))
      (node (ref "C665") (pin "2") (pinfunction "2_2") (pintype "passive"))
      (node (ref "C666") (pin "2") (pinfunction "2_2") (pintype "passive"))
      (node (ref "C667") (pin "2") (pinfunction "2_2") (pintype "passive"))
      (node (ref "C668") (pin "2") (pinfunction "2_2") (pintype "passive"))
      (node (ref "C669") (pin "1") (pinfunction "1_1") (pintype "passive"))
      (node (ref "FR123") (pin "2") (pinfunction "2_2") (pintype "passive"))
      (node (ref "IC54") (pin "16") (pinfunction "AVDD_16") (pintype "power_in"))
      (node (ref "IC54") (pin "22") (pinfunction "AVDD_22") (pintype "power_in"))
      (node (ref "IC54") (pin "33") (pinfunction "AVDD_33") (pintype "power_in"))
      (node (ref "IC54") (pin "34") (pinfunction "AVDD_34") (pintype "power_in"))
    )
    (net (code "73") (name "VCC1P8D_LMS3_BB_ADC1") (class "Default")
      (node (ref "C658") (pin "2") (pinfunction "2_2") (pintype "passive"))
      (node (ref "C659") (pin "2") (pinfunction "2_2") (pintype "passive"))
      (node (ref "C660") (pin "2") (pinfunction "2_2") (pintype "passive"))
      (node (ref "C661") (pin "2") (pinfunction "2_2") (pintype "passive"))
      (node (ref "C662") (pin "1") (pinfunction "1_1") (pintype "passive"))
      (node (ref "FR122") (pin "2") (pinfunction "2_2") (pintype "passive"))
      (node (ref "IC54") (pin "1") (pinfunction "DRVDD_1") (pintype "power_in"))
      (node (ref "IC54") (pin "48") (pinfunction "DRVDD_48") (pintype "power_in"))
      (node (ref "R353") (pin "2") (pinfunction "2_2") (pintype "passive"))
      (node (ref "R355") (pin "2") (pinfunction "2_2") (pintype "passive"))
      (node (ref "R357") (pin "2") (pinfunction "2_2") (pintype "passive"))
    )
    (net (code "74") (name "VCC3P3") (class "Default")
      (node (ref "R359") (pin "2") (pinfunction "2_2") (pintype "passive"))
    )
    (net (code "75") (name "VCC5P0") (class "Default")
      (node (ref "R360") (pin "2") (pinfunction "2_2") (pintype "passive"))
    )
    (net (code "76") (name "VCC_LMS3_BB_ADCDRV1") (class "Default")
      (node (ref "C647") (pin "2") (pinfunction "2_2") (pintype "passive"))
      (node (ref "C648") (pin "1") (pinfunction "1_1") (pintype "passive"))
      (node (ref "C649") (pin "1") (pinfunction "1_1") (pintype "passive"))
      (node (ref "C654") (pin "2") (pinfunction "2_2") (pintype "passive"))
      (node (ref "C655") (pin "1") (pinfunction "1_1") (pintype "passive"))
      (node (ref "C656") (pin "1") (pinfunction "1_1") (pintype "passive"))
      (node (ref "C657") (pin "2") (pinfunction "2_2") (pintype "passive"))
      (node (ref "FR121") (pin "2") (pinfunction "2_2") (pintype "passive"))
      (node (ref "IC55") (pin "10") (pinfunction "+VS2_10") (pintype "power_in"))
      (node (ref "IC55") (pin "3") (pinfunction "+VS1_3") (pintype "power_in"))
      (node (ref "IC55") (pin "4") (pinfunction "+VS1_4") (pintype "power_in"))
      (node (ref "IC55") (pin "9") (pinfunction "+VS2_9") (pintype "power_in"))
      (node (ref "R343") (pin "2") (pinfunction "2_2") (pintype "passive"))
    )
    (net (code "77") (name "unconnected-(FL19-Pad1)") (class "Default")
      (node (ref "FL19") (pin "1") (pintype "passive+no_connect"))
    )
    (net (code "78") (name "unconnected-(IC54C-NC-Pad38)") (class "Default")
      (node (ref "IC54") (pin "38") (pinfunction "NC_38") (pintype "passive+no_connect"))
    )
    (net (code "79") (name "unconnected-(IC54C-NC-Pad39)") (class "Default")
      (node (ref "IC54") (pin "39") (pinfunction "NC_39") (pintype "passive+no_connect"))
    )
    (net (code "80") (name "unconnected-(IC54C-NC-Pad58)") (class "Default")
      (node (ref "IC54") (pin "58") (pinfunction "NC_58") (pintype "passive+no_connect"))
    )
    (net (code "81") (name "unconnected-(IC54C-NC-Pad59)") (class "Default")
      (node (ref "IC54") (pin "59") (pinfunction "NC_59") (pintype "passive+no_connect"))
    )
  )
)
